# untitled.net
KiCad netlist of a schematic drawn in EAGLE
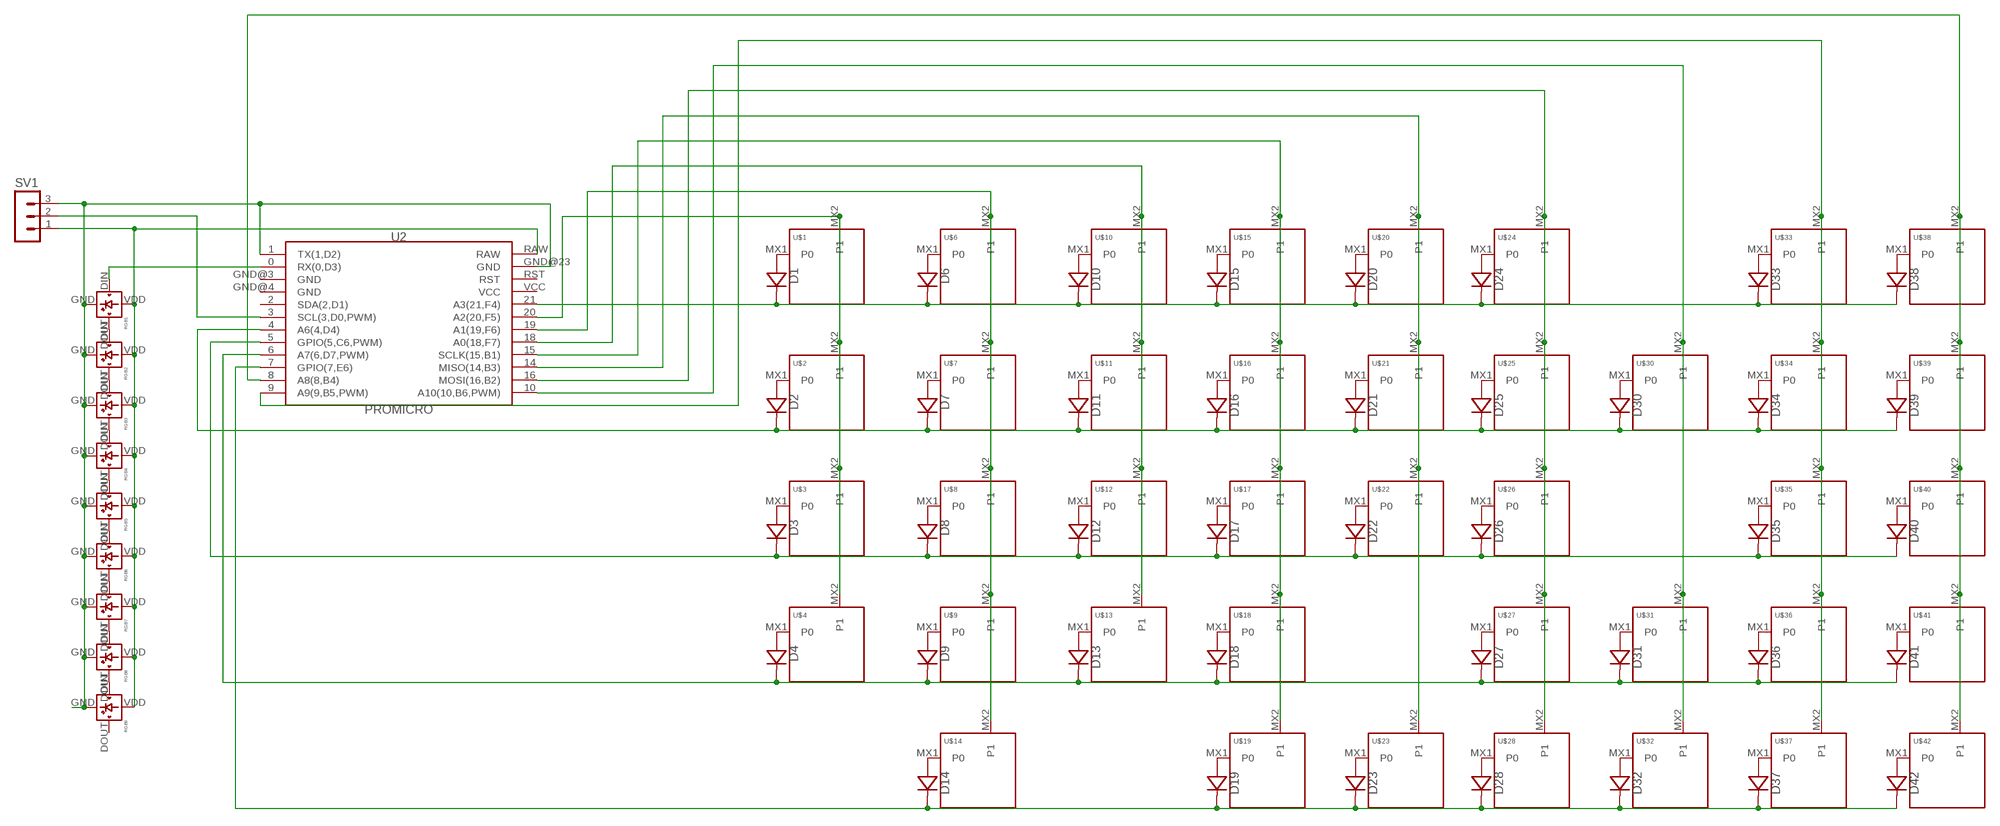
[diagram p0: schematic, sheet 1]

(export (version "E")
  (design (tool "Eeschema 10.0.6"))
  (components
    (comp (ref "D1")
      (value "DIODE-SOD-123")
      (footprint "eagle-import:SOD-123")
      (libsource (lib "eagle-import") (part "DIODE-SOD-123"))
    )
    (comp (ref "D2")
      (value "DIODE-SOD-123")
      (footprint "eagle-import:SOD-123")
      (libsource (lib "eagle-import") (part "DIODE-SOD-123"))
    )
    (comp (ref "D3")
      (value "DIODE-SOD-123")
      (footprint "eagle-import:SOD-123")
      (libsource (lib "eagle-import") (part "DIODE-SOD-123"))
    )
    (comp (ref "D4")
      (value "DIODE-SOD-123")
      (footprint "eagle-import:SOD-123")
      (libsource (lib "eagle-import") (part "DIODE-SOD-123"))
    )
    (comp (ref "D6")
      (value "DIODE-SOD-123")
      (footprint "eagle-import:SOD-123")
      (libsource (lib "eagle-import") (part "DIODE-SOD-123"))
    )
    (comp (ref "D7")
      (value "DIODE-SOD-123")
      (footprint "eagle-import:SOD-123")
      (libsource (lib "eagle-import") (part "DIODE-SOD-123"))
    )
    (comp (ref "D8")
      (value "DIODE-SOD-123")
      (footprint "eagle-import:SOD-123")
      (libsource (lib "eagle-import") (part "DIODE-SOD-123"))
    )
    (comp (ref "D9")
      (value "DIODE-SOD-123")
      (footprint "eagle-import:SOD-123")
      (libsource (lib "eagle-import") (part "DIODE-SOD-123"))
    )
    (comp (ref "D10")
      (value "DIODE-SOD-123")
      (footprint "eagle-import:SOD-123")
      (libsource (lib "eagle-import") (part "DIODE-SOD-123"))
    )
    (comp (ref "D11")
      (value "DIODE-SOD-123")
      (footprint "eagle-import:SOD-123")
      (libsource (lib "eagle-import") (part "DIODE-SOD-123"))
    )
    (comp (ref "D12")
      (value "DIODE-SOD-123")
      (footprint "eagle-import:SOD-123")
      (libsource (lib "eagle-import") (part "DIODE-SOD-123"))
    )
    (comp (ref "D13")
      (value "DIODE-SOD-123")
      (footprint "eagle-import:SOD-123")
      (libsource (lib "eagle-import") (part "DIODE-SOD-123"))
    )
    (comp (ref "D14")
      (value "DIODE-SOD-123")
      (footprint "eagle-import:SOD-123")
      (libsource (lib "eagle-import") (part "DIODE-SOD-123"))
    )
    (comp (ref "D15")
      (value "DIODE-SOD-123")
      (footprint "eagle-import:SOD-123")
      (libsource (lib "eagle-import") (part "DIODE-SOD-123"))
    )
    (comp (ref "D16")
      (value "DIODE-SOD-123")
      (footprint "eagle-import:SOD-123")
      (libsource (lib "eagle-import") (part "DIODE-SOD-123"))
    )
    (comp (ref "D17")
      (value "DIODE-SOD-123")
      (footprint "eagle-import:SOD-123")
      (libsource (lib "eagle-import") (part "DIODE-SOD-123"))
    )
    (comp (ref "D18")
      (value "DIODE-SOD-123")
      (footprint "eagle-import:SOD-123")
      (libsource (lib "eagle-import") (part "DIODE-SOD-123"))
    )
    (comp (ref "D19")
      (value "DIODE-SOD-123")
      (footprint "eagle-import:SOD-123")
      (libsource (lib "eagle-import") (part "DIODE-SOD-123"))
    )
    (comp (ref "D20")
      (value "DIODE-SOD-123")
      (footprint "eagle-import:SOD-123")
      (libsource (lib "eagle-import") (part "DIODE-SOD-123"))
    )
    (comp (ref "D21")
      (value "DIODE-SOD-123")
      (footprint "eagle-import:SOD-123")
      (libsource (lib "eagle-import") (part "DIODE-SOD-123"))
    )
    (comp (ref "D22")
      (value "DIODE-SOD-123")
      (footprint "eagle-import:SOD-123")
      (libsource (lib "eagle-import") (part "DIODE-SOD-123"))
    )
    (comp (ref "D23")
      (value "DIODE-SOD-123")
      (footprint "eagle-import:SOD-123")
      (libsource (lib "eagle-import") (part "DIODE-SOD-123"))
    )
    (comp (ref "D24")
      (value "DIODE-SOD-123")
      (footprint "eagle-import:SOD-123")
      (libsource (lib "eagle-import") (part "DIODE-SOD-123"))
    )
    (comp (ref "D25")
      (value "DIODE-SOD-123")
      (footprint "eagle-import:SOD-123")
      (libsource (lib "eagle-import") (part "DIODE-SOD-123"))
    )
    (comp (ref "D26")
      (value "DIODE-SOD-123")
      (footprint "eagle-import:SOD-123")
      (libsource (lib "eagle-import") (part "DIODE-SOD-123"))
    )
    (comp (ref "D27")
      (value "DIODE-SOD-123")
      (footprint "eagle-import:SOD-123")
      (libsource (lib "eagle-import") (part "DIODE-SOD-123"))
    )
    (comp (ref "D28")
      (value "DIODE-SOD-123")
      (footprint "eagle-import:SOD-123")
      (libsource (lib "eagle-import") (part "DIODE-SOD-123"))
    )
    (comp (ref "D30")
      (value "DIODE-SOD-123")
      (footprint "eagle-import:SOD-123")
      (libsource (lib "eagle-import") (part "DIODE-SOD-123"))
    )
    (comp (ref "D31")
      (value "DIODE-SOD-123")
      (footprint "eagle-import:SOD-123")
      (libsource (lib "eagle-import") (part "DIODE-SOD-123"))
    )
    (comp (ref "D32")
      (value "DIODE-SOD-123")
      (footprint "eagle-import:SOD-123")
      (libsource (lib "eagle-import") (part "DIODE-SOD-123"))
    )
    (comp (ref "D33")
      (value "DIODE-SOD-123")
      (footprint "eagle-import:SOD-123")
      (libsource (lib "eagle-import") (part "DIODE-SOD-123"))
    )
    (comp (ref "D34")
      (value "DIODE-SOD-123")
      (footprint "eagle-import:SOD-123")
      (libsource (lib "eagle-import") (part "DIODE-SOD-123"))
    )
    (comp (ref "D35")
      (value "DIODE-SOD-123")
      (footprint "eagle-import:SOD-123")
      (libsource (lib "eagle-import") (part "DIODE-SOD-123"))
    )
    (comp (ref "D36")
      (value "DIODE-SOD-123")
      (footprint "eagle-import:SOD-123")
      (libsource (lib "eagle-import") (part "DIODE-SOD-123"))
    )
    (comp (ref "D37")
      (value "DIODE-SOD-123")
      (footprint "eagle-import:SOD-123")
      (libsource (lib "eagle-import") (part "DIODE-SOD-123"))
    )
    (comp (ref "D38")
      (value "DIODE-SOD-123")
      (footprint "eagle-import:SOD-123")
      (libsource (lib "eagle-import") (part "DIODE-SOD-123"))
    )
    (comp (ref "D39")
      (value "DIODE-SOD-123")
      (footprint "eagle-import:SOD-123")
      (libsource (lib "eagle-import") (part "DIODE-SOD-123"))
    )
    (comp (ref "D40")
      (value "DIODE-SOD-123")
      (footprint "eagle-import:SOD-123")
      (libsource (lib "eagle-import") (part "DIODE-SOD-123"))
    )
    (comp (ref "D41")
      (value "DIODE-SOD-123")
      (footprint "eagle-import:SOD-123")
      (libsource (lib "eagle-import") (part "DIODE-SOD-123"))
    )
    (comp (ref "D42")
      (value "DIODE-SOD-123")
      (footprint "eagle-import:SOD-123")
      (libsource (lib "eagle-import") (part "DIODE-SOD-123"))
    )
    (comp (ref "RGB1")
      (value "WS2812B-MINI")
      (footprint "eagle-import:WS2812B-MINI")
      (libsource (lib "eagle-import") (part "WS2812B-MINI"))
    )
    (comp (ref "RGB2")
      (value "WS2812B-MINI")
      (footprint "eagle-import:WS2812B-MINI")
      (libsource (lib "eagle-import") (part "WS2812B-MINI"))
    )
    (comp (ref "RGB3")
      (value "WS2812B-MINI")
      (footprint "eagle-import:WS2812B-MINI")
      (libsource (lib "eagle-import") (part "WS2812B-MINI"))
    )
    (comp (ref "RGB4")
      (value "WS2812B-MINI")
      (footprint "eagle-import:WS2812B-MINI")
      (libsource (lib "eagle-import") (part "WS2812B-MINI"))
    )
    (comp (ref "RGB5")
      (value "WS2812B-MINI")
      (footprint "eagle-import:WS2812B-MINI")
      (libsource (lib "eagle-import") (part "WS2812B-MINI"))
    )
    (comp (ref "RGB6")
      (value "WS2812B-MINI")
      (footprint "eagle-import:WS2812B-MINI")
      (libsource (lib "eagle-import") (part "WS2812B-MINI"))
    )
    (comp (ref "RGB7")
      (value "WS2812B-MINI")
      (footprint "eagle-import:WS2812B-MINI")
      (libsource (lib "eagle-import") (part "WS2812B-MINI"))
    )
    (comp (ref "RGB8")
      (value "WS2812B-MINI")
      (footprint "eagle-import:WS2812B-MINI")
      (libsource (lib "eagle-import") (part "WS2812B-MINI"))
    )
    (comp (ref "RGB9")
      (value "WS2812B-MINI")
      (footprint "eagle-import:WS2812B-MINI")
      (libsource (lib "eagle-import") (part "WS2812B-MINI"))
    )
    (comp (ref "SV1")
      (value "MA03-1")
      (footprint "eagle-import:MA03-1")
      (libsource (lib "eagle-import") (part "MA03-1"))
    )
    (comp (ref "U$1")
      (value "KEYSWITCH-PLAIN-MX-1U")
      (footprint "eagle-import:MX-1U")
      (libsource (lib "eagle-import") (part "KEYSWITCH-PLAIN-MX-1U"))
    )
    (comp (ref "U$2")
      (value "KEYSWITCH-PLAIN-MX-1U")
      (footprint "eagle-import:MX-1U")
      (libsource (lib "eagle-import") (part "KEYSWITCH-PLAIN-MX-1U"))
    )
    (comp (ref "U$3")
      (value "KEYSWITCH-PLAIN-MX-1U")
      (footprint "eagle-import:MX-1U")
      (libsource (lib "eagle-import") (part "KEYSWITCH-PLAIN-MX-1U"))
    )
    (comp (ref "U$4")
      (value "KEYSWITCH-PLAIN-MX-1U")
      (footprint "eagle-import:MX-1U")
      (libsource (lib "eagle-import") (part "KEYSWITCH-PLAIN-MX-1U"))
    )
    (comp (ref "U$6")
      (value "KEYSWITCH-PLAIN-MX-1U")
      (footprint "eagle-import:MX-1U")
      (libsource (lib "eagle-import") (part "KEYSWITCH-PLAIN-MX-1U"))
    )
    (comp (ref "U$7")
      (value "KEYSWITCH-PLAIN-MX-1U")
      (footprint "eagle-import:MX-1U")
      (libsource (lib "eagle-import") (part "KEYSWITCH-PLAIN-MX-1U"))
    )
    (comp (ref "U$8")
      (value "KEYSWITCH-PLAIN-MX-1U")
      (footprint "eagle-import:MX-1U")
      (libsource (lib "eagle-import") (part "KEYSWITCH-PLAIN-MX-1U"))
    )
    (comp (ref "U$9")
      (value "KEYSWITCH-PLAIN-MX-1U")
      (footprint "eagle-import:MX-1U")
      (libsource (lib "eagle-import") (part "KEYSWITCH-PLAIN-MX-1U"))
    )
    (comp (ref "U$10")
      (value "KEYSWITCH-PLAIN-MX-1U")
      (footprint "eagle-import:MX-1U")
      (libsource (lib "eagle-import") (part "KEYSWITCH-PLAIN-MX-1U"))
    )
    (comp (ref "U$11")
      (value "KEYSWITCH-PLAIN-MX-1U")
      (footprint "eagle-import:MX-1U")
      (libsource (lib "eagle-import") (part "KEYSWITCH-PLAIN-MX-1U"))
    )
    (comp (ref "U$12")
      (value "KEYSWITCH-PLAIN-MX-1U")
      (footprint "eagle-import:MX-1U")
      (libsource (lib "eagle-import") (part "KEYSWITCH-PLAIN-MX-1U"))
    )
    (comp (ref "U$13")
      (value "KEYSWITCH-PLAIN-MX-1U")
      (footprint "eagle-import:MX-1U")
      (libsource (lib "eagle-import") (part "KEYSWITCH-PLAIN-MX-1U"))
    )
    (comp (ref "U$14")
      (value "KEYSWITCH-PLAIN-MX-1U")
      (footprint "eagle-import:MX-1U")
      (libsource (lib "eagle-import") (part "KEYSWITCH-PLAIN-MX-1U"))
    )
    (comp (ref "U$15")
      (value "KEYSWITCH-PLAIN-MX-1U")
      (footprint "eagle-import:MX-1U")
      (libsource (lib "eagle-import") (part "KEYSWITCH-PLAIN-MX-1U"))
    )
    (comp (ref "U$16")
      (value "KEYSWITCH-PLAIN-MX-1U")
      (footprint "eagle-import:MX-1U")
      (libsource (lib "eagle-import") (part "KEYSWITCH-PLAIN-MX-1U"))
    )
    (comp (ref "U$17")
      (value "KEYSWITCH-PLAIN-MX-1U")
      (footprint "eagle-import:MX-1U")
      (libsource (lib "eagle-import") (part "KEYSWITCH-PLAIN-MX-1U"))
    )
    (comp (ref "U$18")
      (value "KEYSWITCH-PLAIN-MX-1U")
      (footprint "eagle-import:MX-1U")
      (libsource (lib "eagle-import") (part "KEYSWITCH-PLAIN-MX-1U"))
    )
    (comp (ref "U$19")
      (value "KEYSWITCH-PLAIN-MX-1U")
      (footprint "eagle-import:MX-1U")
      (libsource (lib "eagle-import") (part "KEYSWITCH-PLAIN-MX-1U"))
    )
    (comp (ref "U$20")
      (value "KEYSWITCH-PLAIN-MX-1U")
      (footprint "eagle-import:MX-1U")
      (libsource (lib "eagle-import") (part "KEYSWITCH-PLAIN-MX-1U"))
    )
    (comp (ref "U$21")
      (value "KEYSWITCH-PLAIN-MX-1U")
      (footprint "eagle-import:MX-1U")
      (libsource (lib "eagle-import") (part "KEYSWITCH-PLAIN-MX-1U"))
    )
    (comp (ref "U$22")
      (value "KEYSWITCH-PLAIN-MX-1U")
      (footprint "eagle-import:MX-1U")
      (libsource (lib "eagle-import") (part "KEYSWITCH-PLAIN-MX-1U"))
    )
    (comp (ref "U$23")
      (value "KEYSWITCH-PLAIN-MX-1U")
      (footprint "eagle-import:MX-1U")
      (libsource (lib "eagle-import") (part "KEYSWITCH-PLAIN-MX-1U"))
    )
    (comp (ref "U$24")
      (value "KEYSWITCH-PLAIN-MX-1U")
      (footprint "eagle-import:MX-1U")
      (libsource (lib "eagle-import") (part "KEYSWITCH-PLAIN-MX-1U"))
    )
    (comp (ref "U$25")
      (value "KEYSWITCH-PLAIN-MX-1U")
      (footprint "eagle-import:MX-1U")
      (libsource (lib "eagle-import") (part "KEYSWITCH-PLAIN-MX-1U"))
    )
    (comp (ref "U$26")
      (value "KEYSWITCH-PLAIN-MX-1U")
      (footprint "eagle-import:MX-1U")
      (libsource (lib "eagle-import") (part "KEYSWITCH-PLAIN-MX-1U"))
    )
    (comp (ref "U$27")
      (value "KEYSWITCH-PLAIN-MX-1U")
      (footprint "eagle-import:MX-1U")
      (libsource (lib "eagle-import") (part "KEYSWITCH-PLAIN-MX-1U"))
    )
    (comp (ref "U$28")
      (value "KEYSWITCH-PLAIN-MX-1U")
      (footprint "eagle-import:MX-1U")
      (libsource (lib "eagle-import") (part "KEYSWITCH-PLAIN-MX-1U"))
    )
    (comp (ref "U$30")
      (value "KEYSWITCH-PLAIN-MX-1U")
      (footprint "eagle-import:MX-1U")
      (libsource (lib "eagle-import") (part "KEYSWITCH-PLAIN-MX-1U"))
    )
    (comp (ref "U$31")
      (value "KEYSWITCH-PLAIN-MX-1U")
      (footprint "eagle-import:MX-1U")
      (libsource (lib "eagle-import") (part "KEYSWITCH-PLAIN-MX-1U"))
    )
    (comp (ref "U$32")
      (value "KEYSWITCH-PLAIN-MX-1U")
      (footprint "eagle-import:MX-1U")
      (libsource (lib "eagle-import") (part "KEYSWITCH-PLAIN-MX-1U"))
    )
    (comp (ref "U$33")
      (value "KEYSWITCH-PLAIN-MX-1U")
      (footprint "eagle-import:MX-1U")
      (libsource (lib "eagle-import") (part "KEYSWITCH-PLAIN-MX-1U"))
    )
    (comp (ref "U$34")
      (value "KEYSWITCH-PLAIN-MX-1U")
      (footprint "eagle-import:MX-1U")
      (libsource (lib "eagle-import") (part "KEYSWITCH-PLAIN-MX-1U"))
    )
    (comp (ref "U$35")
      (value "KEYSWITCH-PLAIN-MX-1U")
      (footprint "eagle-import:MX-1U")
      (libsource (lib "eagle-import") (part "KEYSWITCH-PLAIN-MX-1U"))
    )
    (comp (ref "U$36")
      (value "KEYSWITCH-PLAIN-MX-1U")
      (footprint "eagle-import:MX-1U")
      (libsource (lib "eagle-import") (part "KEYSWITCH-PLAIN-MX-1U"))
    )
    (comp (ref "U$37")
      (value "KEYSWITCH-PLAIN-MX-1U")
      (footprint "eagle-import:MX-1U")
      (libsource (lib "eagle-import") (part "KEYSWITCH-PLAIN-MX-1U"))
    )
    (comp (ref "U$38")
      (value "KEYSWITCH-PLAIN-MX-1U")
      (footprint "eagle-import:MX-1U")
      (libsource (lib "eagle-import") (part "KEYSWITCH-PLAIN-MX-1U"))
    )
    (comp (ref "U$39")
      (value "KEYSWITCH-PLAIN-MX-1U")
      (footprint "eagle-import:MX-1U")
      (libsource (lib "eagle-import") (part "KEYSWITCH-PLAIN-MX-1U"))
    )
    (comp (ref "U$40")
      (value "KEYSWITCH-PLAIN-MX-1U")
      (footprint "eagle-import:MX-1U")
      (libsource (lib "eagle-import") (part "KEYSWITCH-PLAIN-MX-1U"))
    )
    (comp (ref "U$41")
      (value "KEYSWITCH-PLAIN-MX-1U")
      (footprint "eagle-import:MX-1U")
      (libsource (lib "eagle-import") (part "KEYSWITCH-PLAIN-MX-1U"))
    )
    (comp (ref "U$42")
      (value "KEYSWITCH-PLAIN-MX-1U")
      (footprint "eagle-import:MX-1U")
      (libsource (lib "eagle-import") (part "KEYSWITCH-PLAIN-MX-1U"))
    )
    (comp (ref "U2")
      (value "PROMICRO")
      (footprint "eagle-import:PROMICRO")
      (libsource (lib "eagle-import") (part "PROMICRO"))
    )
  )
  (nets
    (net (code "1") (name "Net-(RGB1-PadDOUT)") (class "Default")
      (node (ref "RGB1") (pin "DOUT") (pinfunction "DOUT_DOUT") (pintype "output"))
      (node (ref "RGB2") (pin "DIN") (pinfunction "DIN_DIN") (pintype "input"))
    )
    (net (code "2") (name "Net-(RGB1-PadVDD)") (class "Default")
      (node (ref "RGB1") (pin "VDD") (pinfunction "VDD_VDD") (pintype "bidirectional"))
      (node (ref "RGB2") (pin "VDD") (pinfunction "VDD_VDD") (pintype "bidirectional"))
      (node (ref "RGB3") (pin "VDD") (pinfunction "VDD_VDD") (pintype "bidirectional"))
      (node (ref "RGB4") (pin "VDD") (pinfunction "VDD_VDD") (pintype "bidirectional"))
      (node (ref "RGB5") (pin "VDD") (pinfunction "VDD_VDD") (pintype "bidirectional"))
      (node (ref "RGB6") (pin "VDD") (pinfunction "VDD_VDD") (pintype "bidirectional"))
      (node (ref "RGB7") (pin "VDD") (pinfunction "VDD_VDD") (pintype "bidirectional"))
      (node (ref "RGB8") (pin "VDD") (pinfunction "VDD_VDD") (pintype "bidirectional"))
      (node (ref "RGB9") (pin "VDD") (pinfunction "VDD_VDD") (pintype "bidirectional"))
      (node (ref "SV1") (pin "1") (pinfunction "1_1") (pintype "passive"))
      (node (ref "U2") (pin "RAW") (pinfunction "RAW_RAW") (pintype "bidirectional"))
    )
    (net (code "3") (name "Net-(RGB2-PadDOUT)") (class "Default")
      (node (ref "RGB2") (pin "DOUT") (pinfunction "DOUT_DOUT") (pintype "output"))
      (node (ref "RGB3") (pin "DIN") (pinfunction "DIN_DIN") (pintype "input"))
    )
    (net (code "4") (name "Net-(RGB3-PadDOUT)") (class "Default")
      (node (ref "RGB3") (pin "DOUT") (pinfunction "DOUT_DOUT") (pintype "output"))
      (node (ref "RGB4") (pin "DIN") (pinfunction "DIN_DIN") (pintype "input"))
    )
    (net (code "5") (name "Net-(RGB4-PadDOUT)") (class "Default")
      (node (ref "RGB4") (pin "DOUT") (pinfunction "DOUT_DOUT") (pintype "output"))
      (node (ref "RGB5") (pin "DIN") (pinfunction "DIN_DIN") (pintype "input"))
    )
    (net (code "6") (name "Net-(RGB5-PadDOUT)") (class "Default")
      (node (ref "RGB5") (pin "DOUT") (pinfunction "DOUT_DOUT") (pintype "output"))
      (node (ref "RGB6") (pin "DIN") (pinfunction "DIN_DIN") (pintype "input"))
    )
    (net (code "7") (name "Net-(RGB6-PadDOUT)") (class "Default")
      (node (ref "RGB6") (pin "DOUT") (pinfunction "DOUT_DOUT") (pintype "output"))
      (node (ref "RGB7") (pin "DIN") (pinfunction "DIN_DIN") (pintype "input"))
    )
    (net (code "8") (name "Net-(RGB7-PadDOUT)") (class "Default")
      (node (ref "RGB7") (pin "DOUT") (pinfunction "DOUT_DOUT") (pintype "output"))
      (node (ref "RGB8") (pin "DIN") (pinfunction "DIN_DIN") (pintype "input"))
    )
    (net (code "9") (name "Net-(RGB8-PadDOUT)") (class "Default")
      (node (ref "RGB8") (pin "DOUT") (pinfunction "DOUT_DOUT") (pintype "output"))
      (node (ref "RGB9") (pin "DIN") (pinfunction "DIN_DIN") (pintype "input"))
    )
    (net (code "10") (name "Net-(U$1-P0)") (class "Default")
      (node (ref "D1") (pin "A") (pinfunction "A_A") (pintype "passive"))
      (node (ref "U$1") (pin "MX1") (pinfunction "P0_MX1") (pintype "bidirectional"))
    )
    (net (code "11") (name "Net-(U$1-P1)") (class "Default")
      (node (ref "U$1") (pin "MX2") (pinfunction "P1_MX2") (pintype "bidirectional"))
      (node (ref "U$2") (pin "MX2") (pinfunction "P1_MX2") (pintype "bidirectional"))
      (node (ref "U$3") (pin "MX2") (pinfunction "P1_MX2") (pintype "bidirectional"))
      (node (ref "U$4") (pin "MX2") (pinfunction "P1_MX2") (pintype "bidirectional"))
      (node (ref "U2") (pin "20") (pinfunction "A2(20,F5)_20") (pintype "bidirectional"))
    )
    (net (code "12") (name "Net-(U$2-P0)") (class "Default")
      (node (ref "D2") (pin "A") (pinfunction "A_A") (pintype "passive"))
      (node (ref "U$2") (pin "MX1") (pinfunction "P0_MX1") (pintype "bidirectional"))
    )
    (net (code "13") (name "Net-(U$3-P0)") (class "Default")
      (node (ref "D3") (pin "A") (pinfunction "A_A") (pintype "passive"))
      (node (ref "U$3") (pin "MX1") (pinfunction "P0_MX1") (pintype "bidirectional"))
    )
    (net (code "14") (name "Net-(U$4-P0)") (class "Default")
      (node (ref "D4") (pin "A") (pinfunction "A_A") (pintype "passive"))
      (node (ref "U$4") (pin "MX1") (pinfunction "P0_MX1") (pintype "bidirectional"))
    )
    (net (code "15") (name "Net-(U$6-P0)") (class "Default")
      (node (ref "D6") (pin "A") (pinfunction "A_A") (pintype "passive"))
      (node (ref "U$6") (pin "MX1") (pinfunction "P0_MX1") (pintype "bidirectional"))
    )
    (net (code "16") (name "Net-(U$7-P0)") (class "Default")
      (node (ref "D7") (pin "A") (pinfunction "A_A") (pintype "passive"))
      (node (ref "U$7") (pin "MX1") (pinfunction "P0_MX1") (pintype "bidirectional"))
    )
    (net (code "17") (name "Net-(U$8-P0)") (class "Default")
      (node (ref "D8") (pin "A") (pinfunction "A_A") (pintype "passive"))
      (node (ref "U$8") (pin "MX1") (pinfunction "P0_MX1") (pintype "bidirectional"))
    )
    (net (code "18") (name "Net-(U$9-P0)") (class "Default")
      (node (ref "D9") (pin "A") (pinfunction "A_A") (pintype "passive"))
      (node (ref "U$9") (pin "MX1") (pinfunction "P0_MX1") (pintype "bidirectional"))
    )
    (net (code "19") (name "Net-(U$10-P0)") (class "Default")
      (node (ref "D10") (pin "A") (pinfunction "A_A") (pintype "passive"))
      (node (ref "U$10") (pin "MX1") (pinfunction "P0_MX1") (pintype "bidirectional"))
    )
    (net (code "20") (name "Net-(U$10-P1)") (class "Default")
      (node (ref "U$10") (pin "MX2") (pinfunction "P1_MX2") (pintype "bidirectional"))
      (node (ref "U$11") (pin "MX2") (pinfunction "P1_MX2") (pintype "bidirectional"))
      (node (ref "U$12") (pin "MX2") (pinfunction "P1_MX2") (pintype "bidirectional"))
      (node (ref "U$13") (pin "MX2") (pinfunction "P1_MX2") (pintype "bidirectional"))
      (node (ref "U2") (pin "18") (pinfunction "A0(18,F7)_18") (pintype "bidirectional"))
    )
    (net (code "21") (name "Net-(U$11-P0)") (class "Default")
      (node (ref "D11") (pin "A") (pinfunction "A_A") (pintype "passive"))
      (node (ref "U$11") (pin "MX1") (pinfunction "P0_MX1") (pintype "bidirectional"))
    )
    (net (code "22") (name "Net-(U$12-P0)") (class "Default")
      (node (ref "D12") (pin "A") (pinfunction "A_A") (pintype "passive"))
      (node (ref "U$12") (pin "MX1") (pinfunction "P0_MX1") (pintype "bidirectional"))
    )
    (net (code "23") (name "Net-(U$13-P0)") (class "Default")
      (node (ref "D13") (pin "A") (pinfunction "A_A") (pintype "passive"))
      (node (ref "U$13") (pin "MX1") (pinfunction "P0_MX1") (pintype "bidirectional"))
    )
    (net (code "24") (name "Net-(U$14-P0)") (class "Default")
      (node (ref "D14") (pin "A") (pinfunction "A_A") (pintype "passive"))
      (node (ref "U$14") (pin "MX1") (pinfunction "P0_MX1") (pintype "bidirectional"))
    )
    (net (code "25") (name "Net-(U$14-P1)") (class "Default")
      (node (ref "U$14") (pin "MX2") (pinfunction "P1_MX2") (pintype "bidirectional"))
      (node (ref "U$6") (pin "MX2") (pinfunction "P1_MX2") (pintype "bidirectional"))
      (node (ref "U$7") (pin "MX2") (pinfunction "P1_MX2") (pintype "bidirectional"))
      (node (ref "U$8") (pin "MX2") (pinfunction "P1_MX2") (pintype "bidirectional"))
      (node (ref "U$9") (pin "MX2") (pinfunction "P1_MX2") (pintype "bidirectional"))
      (node (ref "U2") (pin "19") (pinfunction "A1(19,F6)_19") (pintype "bidirectional"))
    )
    (net (code "26") (name "Net-(U$15-P0)") (class "Default")
      (node (ref "D15") (pin "A") (pinfunction "A_A") (pintype "passive"))
      (node (ref "U$15") (pin "MX1") (pinfunction "P0_MX1") (pintype "bidirectional"))
    )
    (net (code "27") (name "Net-(U$15-P1)") (class "Default")
      (node (ref "U$15") (pin "MX2") (pinfunction "P1_MX2") (pintype "bidirectional"))
      (node (ref "U$16") (pin "MX2") (pinfunction "P1_MX2") (pintype "bidirectional"))
      (node (ref "U$17") (pin "MX2") (pinfunction "P1_MX2") (pintype "bidirectional"))
      (node (ref "U$18") (pin "MX2") (pinfunction "P1_MX2") (pintype "bidirectional"))
      (node (ref "U$19") (pin "MX2") (pinfunction "P1_MX2") (pintype "bidirectional"))
      (node (ref "U2") (pin "15") (pinfunction "SCLK(15,B1)_15") (pintype "bidirectional"))
    )
    (net (code "28") (name "Net-(U$16-P0)") (class "Default")
      (node (ref "D16") (pin "A") (pinfunction "A_A") (pintype "passive"))
      (node (ref "U$16") (pin "MX1") (pinfunction "P0_MX1") (pintype "bidirectional"))
    )
    (net (code "29") (name "Net-(U$17-P0)") (class "Default")
      (node (ref "D17") (pin "A") (pinfunction "A_A") (pintype "passive"))
      (node (ref "U$17") (pin "MX1") (pinfunction "P0_MX1") (pintype "bidirectional"))
    )
    (net (code "30") (name "Net-(U$18-P0)") (class "Default")
      (node (ref "D18") (pin "A") (pinfunction "A_A") (pintype "passive"))
      (node (ref "U$18") (pin "MX1") (pinfunction "P0_MX1") (pintype "bidirectional"))
    )
    (net (code "31") (name "Net-(U$19-P0)") (class "Default")
      (node (ref "D19") (pin "A") (pinfunction "A_A") (pintype "passive"))
      (node (ref "U$19") (pin "MX1") (pinfunction "P0_MX1") (pintype "bidirectional"))
    )
    (net (code "32") (name "Net-(U$20-P0)") (class "Default")
      (node (ref "D20") (pin "A") (pinfunction "A_A") (pintype "passive"))
      (node (ref "U$20") (pin "MX1") (pinfunction "P0_MX1") (pintype "bidirectional"))
    )
    (net (code "33") (name "Net-(U$20-P1)") (class "Default")
      (node (ref "U$20") (pin "MX2") (pinfunction "P1_MX2") (pintype "bidirectional"))
      (node (ref "U$21") (pin "MX2") (pinfunction "P1_MX2") (pintype "bidirectional"))
      (node (ref "U$22") (pin "MX2") (pinfunction "P1_MX2") (pintype "bidirectional"))
      (node (ref "U$23") (pin "MX2") (pinfunction "P1_MX2") (pintype "bidirectional"))
      (node (ref "U2") (pin "14") (pinfunction "MISO(14,B3)_14") (pintype "bidirectional"))
    )
    (net (code "34") (name "Net-(U$21-P0)") (class "Default")
      (node (ref "D21") (pin "A") (pinfunction "A_A") (pintype "passive"))
      (node (ref "U$21") (pin "MX1") (pinfunction "P0_MX1") (pintype "bidirectional"))
    )
    (net (code "35") (name "Net-(U$22-P0)") (class "Default")
      (node (ref "D22") (pin "A") (pinfunction "A_A") (pintype "passive"))
      (node (ref "U$22") (pin "MX1") (pinfunction "P0_MX1") (pintype "bidirectional"))
    )
    (net (code "36") (name "Net-(U$23-P0)") (class "Default")
      (node (ref "D23") (pin "A") (pinfunction "A_A") (pintype "passive"))
      (node (ref "U$23") (pin "MX1") (pinfunction "P0_MX1") (pintype "bidirectional"))
    )
    (net (code "37") (name "Net-(U$24-P0)") (class "Default")
      (node (ref "D24") (pin "A") (pinfunction "A_A") (pintype "passive"))
      (node (ref "U$24") (pin "MX1") (pinfunction "P0_MX1") (pintype "bidirectional"))
    )
    (net (code "38") (name "Net-(U$24-P1)") (class "Default")
      (node (ref "U$24") (pin "MX2") (pinfunction "P1_MX2") (pintype "bidirectional"))
      (node (ref "U$25") (pin "MX2") (pinfunction "P1_MX2") (pintype "bidirectional"))
      (node (ref "U$26") (pin "MX2") (pinfunction "P1_MX2") (pintype "bidirectional"))
      (node (ref "U$27") (pin "MX2") (pinfunction "P1_MX2") (pintype "bidirectional"))
      (node (ref "U$28") (pin "MX2") (pinfunction "P1_MX2") (pintype "bidirectional"))
      (node (ref "U2") (pin "16") (pinfunction "MOSI(16,B2)_16") (pintype "bidirectional"))
    )
    (net (code "39") (name "Net-(U$25-P0)") (class "Default")
      (node (ref "D25") (pin "A") (pinfunction "A_A") (pintype "passive"))
      (node (ref "U$25") (pin "MX1") (pinfunction "P0_MX1") (pintype "bidirectional"))
    )
    (net (code "40") (name "Net-(U$26-P0)") (class "Default")
      (node (ref "D26") (pin "A") (pinfunction "A_A") (pintype "passive"))
      (node (ref "U$26") (pin "MX1") (pinfunction "P0_MX1") (pintype "bidirectional"))
    )
    (net (code "41") (name "Net-(U$27-P0)") (class "Default")
      (node (ref "D27") (pin "A") (pinfunction "A_A") (pintype "passive"))
      (node (ref "U$27") (pin "MX1") (pinfunction "P0_MX1") (pintype "bidirectional"))
    )
    (net (code "42") (name "Net-(U$28-P0)") (class "Default")
      (node (ref "D28") (pin "A") (pinfunction "A_A") (pintype "passive"))
      (node (ref "U$28") (pin "MX1") (pinfunction "P0_MX1") (pintype "bidirectional"))
    )
    (net (code "43") (name "Net-(U$30-P0)") (class "Default")
      (node (ref "D30") (pin "A") (pinfunction "A_A") (pintype "passive"))
      (node (ref "U$30") (pin "MX1") (pinfunction "P0_MX1") (pintype "bidirectional"))
    )
    (net (code "44") (name "Net-(U$30-P1)") (class "Default")
      (node (ref "U$30") (pin "MX2") (pinfunction "P1_MX2") (pintype "bidirectional"))
      (node (ref "U$31") (pin "MX2") (pinfunction "P1_MX2") (pintype "bidirectional"))
      (node (ref "U$32") (pin "MX2") (pinfunction "P1_MX2") (pintype "bidirectional"))
      (node (ref "U2") (pin "10") (pinfunction "A10(10,B6,PWM)_10") (pintype "bidirectional"))
    )
    (net (code "45") (name "Net-(U$31-P0)") (class "Default")
      (node (ref "D31") (pin "A") (pinfunction "A_A") (pintype "passive"))
      (node (ref "U$31") (pin "MX1") (pinfunction "P0_MX1") (pintype "bidirectional"))
    )
    (net (code "46") (name "Net-(U$32-P0)") (class "Default")
      (node (ref "D32") (pin "A") (pinfunction "A_A") (pintype "passive"))
      (node (ref "U$32") (pin "MX1") (pinfunction "P0_MX1") (pintype "bidirectional"))
    )
    (net (code "47") (name "Net-(U$33-P0)") (class "Default")
      (node (ref "D33") (pin "A") (pinfunction "A_A") (pintype "passive"))
      (node (ref "U$33") (pin "MX1") (pinfunction "P0_MX1") (pintype "bidirectional"))
    )
    (net (code "48") (name "Net-(U$33-P1)") (class "Default")
      (node (ref "U$33") (pin "MX2") (pinfunction "P1_MX2") (pintype "bidirectional"))
      (node (ref "U$34") (pin "MX2") (pinfunction "P1_MX2") (pintype "bidirectional"))
      (node (ref "U$35") (pin "MX2") (pinfunction "P1_MX2") (pintype "bidirectional"))
      (node (ref "U$36") (pin "MX2") (pinfunction "P1_MX2") (pintype "bidirectional"))
      (node (ref "U$37") (pin "MX2") (pinfunction "P1_MX2") (pintype "bidirectional"))
      (node (ref "U2") (pin "9") (pinfunction "A9(9,B5,PWM)_9") (pintype "bidirectional"))
    )
    (net (code "49") (name "Net-(U$34-P0)") (class "Default")
      (node (ref "D34") (pin "A") (pinfunction "A_A") (pintype "passive"))
      (node (ref "U$34") (pin "MX1") (pinfunction "P0_MX1") (pintype "bidirectional"))
    )
    (net (code "50") (name "Net-(U$35-P0)") (class "Default")
      (node (ref "D35") (pin "A") (pinfunction "A_A") (pintype "passive"))
      (node (ref "U$35") (pin "MX1") (pinfunction "P0_MX1") (pintype "bidirectional"))
    )
    (net (code "51") (name "Net-(U$36-P0)") (class "Default")
      (node (ref "D36") (pin "A") (pinfunction "A_A") (pintype "passive"))
      (node (ref "U$36") (pin "MX1") (pinfunction "P0_MX1") (pintype "bidirectional"))
    )
    (net (code "52") (name "Net-(U$37-P0)") (class "Default")
      (node (ref "D37") (pin "A") (pinfunction "A_A") (pintype "passive"))
      (node (ref "U$37") (pin "MX1") (pinfunction "P0_MX1") (pintype "bidirectional"))
    )
    (net (code "53") (name "Net-(U$38-P0)") (class "Default")
      (node (ref "D38") (pin "A") (pinfunction "A_A") (pintype "passive"))
      (node (ref "U$38") (pin "MX1") (pinfunction "P0_MX1") (pintype "bidirectional"))
    )
    (net (code "54") (name "Net-(U$38-P1)") (class "Default")
      (node (ref "U$38") (pin "MX2") (pinfunction "P1_MX2") (pintype "bidirectional"))
      (node (ref "U$39") (pin "MX2") (pinfunction "P1_MX2") (pintype "bidirectional"))
      (node (ref "U$40") (pin "MX2") (pinfunction "P1_MX2") (pintype "bidirectional"))
      (node (ref "U$41") (pin "MX2") (pinfunction "P1_MX2") (pintype "bidirectional"))
      (node (ref "U$42") (pin "MX2") (pinfunction "P1_MX2") (pintype "bidirectional"))
      (node (ref "U2") (pin "8") (pinfunction "A8(8,B4)_8") (pintype "bidirectional"))
    )
    (net (code "55") (name "Net-(U$39-P0)") (class "Default")
      (node (ref "D39") (pin "A") (pinfunction "A_A") (pintype "passive"))
      (node (ref "U$39") (pin "MX1") (pinfunction "P0_MX1") (pintype "bidirectional"))
    )
    (net (code "56") (name "Net-(U$40-P0)") (class "Default")
      (node (ref "D40") (pin "A") (pinfunction "A_A") (pintype "passive"))
      (node (ref "U$40") (pin "MX1") (pinfunction "P0_MX1") (pintype "bidirectional"))
    )
    (net (code "57") (name "Net-(U$41-P0)") (class "Default")
      (node (ref "D41") (pin "A") (pinfunction "A_A") (pintype "passive"))
      (node (ref "U$41") (pin "MX1") (pinfunction "P0_MX1") (pintype "bidirectional"))
    )
    (net (code "58") (name "Net-(U$42-P0)") (class "Default")
      (node (ref "D42") (pin "A") (pinfunction "A_A") (pintype "passive"))
      (node (ref "U$42") (pin "MX1") (pinfunction "P0_MX1") (pintype "bidirectional"))
    )
    (net (code "59") (name "Net-(U2-A3(21,F4))") (class "Default")
      (node (ref "D1") (pin "C") (pinfunction "C_C") (pintype "passive"))
      (node (ref "D10") (pin "C") (pinfunction "C_C") (pintype "passive"))
      (node (ref "D15") (pin "C") (pinfunction "C_C") (pintype "passive"))
      (node (ref "D20") (pin "C") (pinfunction "C_C") (pintype "passive"))
      (node (ref "D24") (pin "C") (pinfunction "C_C") (pintype "passive"))
      (node (ref "D33") (pin "C") (pinfunction "C_C") (pintype "passive"))
      (node (ref "D38") (pin "C") (pinfunction "C_C") (pintype "passive"))
      (node (ref "D6") (pin "C") (pinfunction "C_C") (pintype "passive"))
      (node (ref "U2") (pin "21") (pinfunction "A3(21,F4)_21") (pintype "bidirectional"))
    )
    (net (code "60") (name "Net-(U2-A6(4,D4))") (class "Default")
      (node (ref "D11") (pin "C") (pinfunction "C_C") (pintype "passive"))
      (node (ref "D16") (pin "C") (pinfunction "C_C") (pintype "passive"))
      (node (ref "D2") (pin "C") (pinfunction "C_C") (pintype "passive"))
      (node (ref "D21") (pin "C") (pinfunction "C_C") (pintype "passive"))
      (node (ref "D25") (pin "C") (pinfunction "C_C") (pintype "passive"))
      (node (ref "D30") (pin "C") (pinfunction "C_C") (pintype "passive"))
      (node (ref "D34") (pin "C") (pinfunction "C_C") (pintype "passive"))
      (node (ref "D39") (pin "C") (pinfunction "C_C") (pintype "passive"))
      (node (ref "D7") (pin "C") (pinfunction "C_C") (pintype "passive"))
      (node (ref "U2") (pin "4") (pinfunction "A6(4,D4)_4") (pintype "bidirectional"))
    )
    (net (code "61") (name "Net-(U2-A7(6,D7,PWM))") (class "Default")
      (node (ref "D13") (pin "C") (pinfunction "C_C") (pintype "passive"))
      (node (ref "D18") (pin "C") (pinfunction "C_C") (pintype "passive"))
      (node (ref "D27") (pin "C") (pinfunction "C_C") (pintype "passive"))
      (node (ref "D31") (pin "C") (pinfunction "C_C") (pintype "passive"))
      (node (ref "D36") (pin "C") (pinfunction "C_C") (pintype "passive"))
      (node (ref "D4") (pin "C") (pinfunction "C_C") (pintype "passive"))
      (node (ref "D41") (pin "C") (pinfunction "C_C") (pintype "passive"))
      (node (ref "D9") (pin "C") (pinfunction "C_C") (pintype "passive"))
      (node (ref "U2") (pin "6") (pinfunction "A7(6,D7,PWM)_6") (pintype "bidirectional"))
    )
    (net (code "62") (name "Net-(U2-GPIO(5,C6,PWM))") (class "Default")
      (node (ref "D12") (pin "C") (pinfunction "C_C") (pintype "passive"))
      (node (ref "D17") (pin "C") (pinfunction "C_C") (pintype "passive"))
      (node (ref "D22") (pin "C") (pinfunction "C_C") (pintype "passive"))
      (node (ref "D26") (pin "C") (pinfunction "C_C") (pintype "passive"))
      (node (ref "D3") (pin "C") (pinfunction "C_C") (pintype "passive"))
      (node (ref "D35") (pin "C") (pinfunction "C_C") (pintype "passive"))
      (node (ref "D40") (pin "C") (pinfunction "C_C") (pintype "passive"))
      (node (ref "D8") (pin "C") (pinfunction "C_C") (pintype "passive"))
      (node (ref "U2") (pin "5") (pinfunction "GPIO(5,C6,PWM)_5") (pintype "bidirectional"))
    )
    (net (code "63") (name "Net-(U2-GPIO(7,E6))") (class "Default")
      (node (ref "D14") (pin "C") (pinfunction "C_C") (pintype "passive"))
      (node (ref "D19") (pin "C") (pinfunction "C_C") (pintype "passive"))
      (node (ref "D23") (pin "C") (pinfunction "C_C") (pintype "passive"))
      (node (ref "D28") (pin "C") (pinfunction "C_C") (pintype "passive"))
      (node (ref "D32") (pin "C") (pinfunction "C_C") (pintype "passive"))
      (node (ref "D37") (pin "C") (pinfunction "C_C") (pintype "passive"))
      (node (ref "D42") (pin "C") (pinfunction "C_C") (pintype "passive"))
      (node (ref "U2") (pin "7") (pinfunction "GPIO(7,E6)_7") (pintype "bidirectional"))
    )
    (net (code "64") (name "Net-(U2-RX(0,D3))") (class "Default")
      (node (ref "RGB1") (pin "DIN") (pinfunction "DIN_DIN") (pintype "input"))
      (node (ref "U2") (pin "0") (pinfunction "RX(0,D3)_0") (pintype "bidirectional"))
    )
    (net (code "65") (name "Net-(U2-SCL(3,D0,PWM))") (class "Default")
      (node (ref "SV1") (pin "2") (pinfunction "2_2") (pintype "passive"))
      (node (ref "U2") (pin "3") (pinfunction "SCL(3,D0,PWM)_3") (pintype "bidirectional"))
    )
    (net (code "66") (name "Net-(U2-TX(1,D2))") (class "Default")
      (node (ref "RGB1") (pin "GND") (pinfunction "GND_GND") (pintype "bidirectional"))
      (node (ref "RGB2") (pin "GND") (pinfunction "GND_GND") (pintype "bidirectional"))
      (node (ref "RGB3") (pin "GND") (pinfunction "GND_GND") (pintype "bidirectional"))
      (node (ref "RGB4") (pin "GND") (pinfunction "GND_GND") (pintype "bidirectional"))
      (node (ref "RGB5") (pin "GND") (pinfunction "GND_GND") (pintype "bidirectional"))
      (node (ref "RGB6") (pin "GND") (pinfunction "GND_GND") (pintype "bidirectional"))
      (node (ref "RGB7") (pin "GND") (pinfunction "GND_GND") (pintype "bidirectional"))
      (node (ref "RGB8") (pin "GND") (pinfunction "GND_GND") (pintype "bidirectional"))
      (node (ref "RGB9") (pin "GND") (pinfunction "GND_GND") (pintype "bidirectional"))
      (node (ref "SV1") (pin "3") (pinfunction "3_3") (pintype "passive"))
      (node (ref "U2") (pin "1") (pinfunction "TX(1,D2)_1") (pintype "bidirectional"))
      (node (ref "U2") (pin "GND@23") (pinfunction "GND_GND@23") (pintype "bidirectional"))
    )
    (net (code "67") (name "unconnected-(RGB9-PadDOUT)") (class "Default")
      (node (ref "RGB9") (pin "DOUT") (pinfunction "DOUT_DOUT") (pintype "output"))
    )
    (net (code "68") (name "unconnected-(U2-GND-PadGND@3)") (class "Default")
      (node (ref "U2") (pin "GND@3") (pinfunction "GND_GND@3") (pintype "bidirectional"))
    )
    (net (code "69") (name "unconnected-(U2-GND-PadGND@4)") (class "Default")
      (node (ref "U2") (pin "GND@4") (pinfunction "GND_GND@4") (pintype "bidirectional"))
    )
    (net (code "70") (name "unconnected-(U2-PadRST)") (class "Default")
      (node (ref "U2") (pin "RST") (pinfunction "RST_RST") (pintype "bidirectional"))
    )
    (net (code "71") (name "unconnected-(U2-PadVCC)") (class "Default")
      (node (ref "U2") (pin "VCC") (pinfunction "VCC_VCC") (pintype "bidirectional"))
    )
    (net (code "72") (name "unconnected-(U2-SDA(2,D1)-Pad2)") (class "Default")
      (node (ref "U2") (pin "2") (pinfunction "SDA(2,D1)_2") (pintype "bidirectional"))
    )
  )
)
